# PWM_CONTROL.net
KiCad netlist of a schematic drawn in Altium Designer
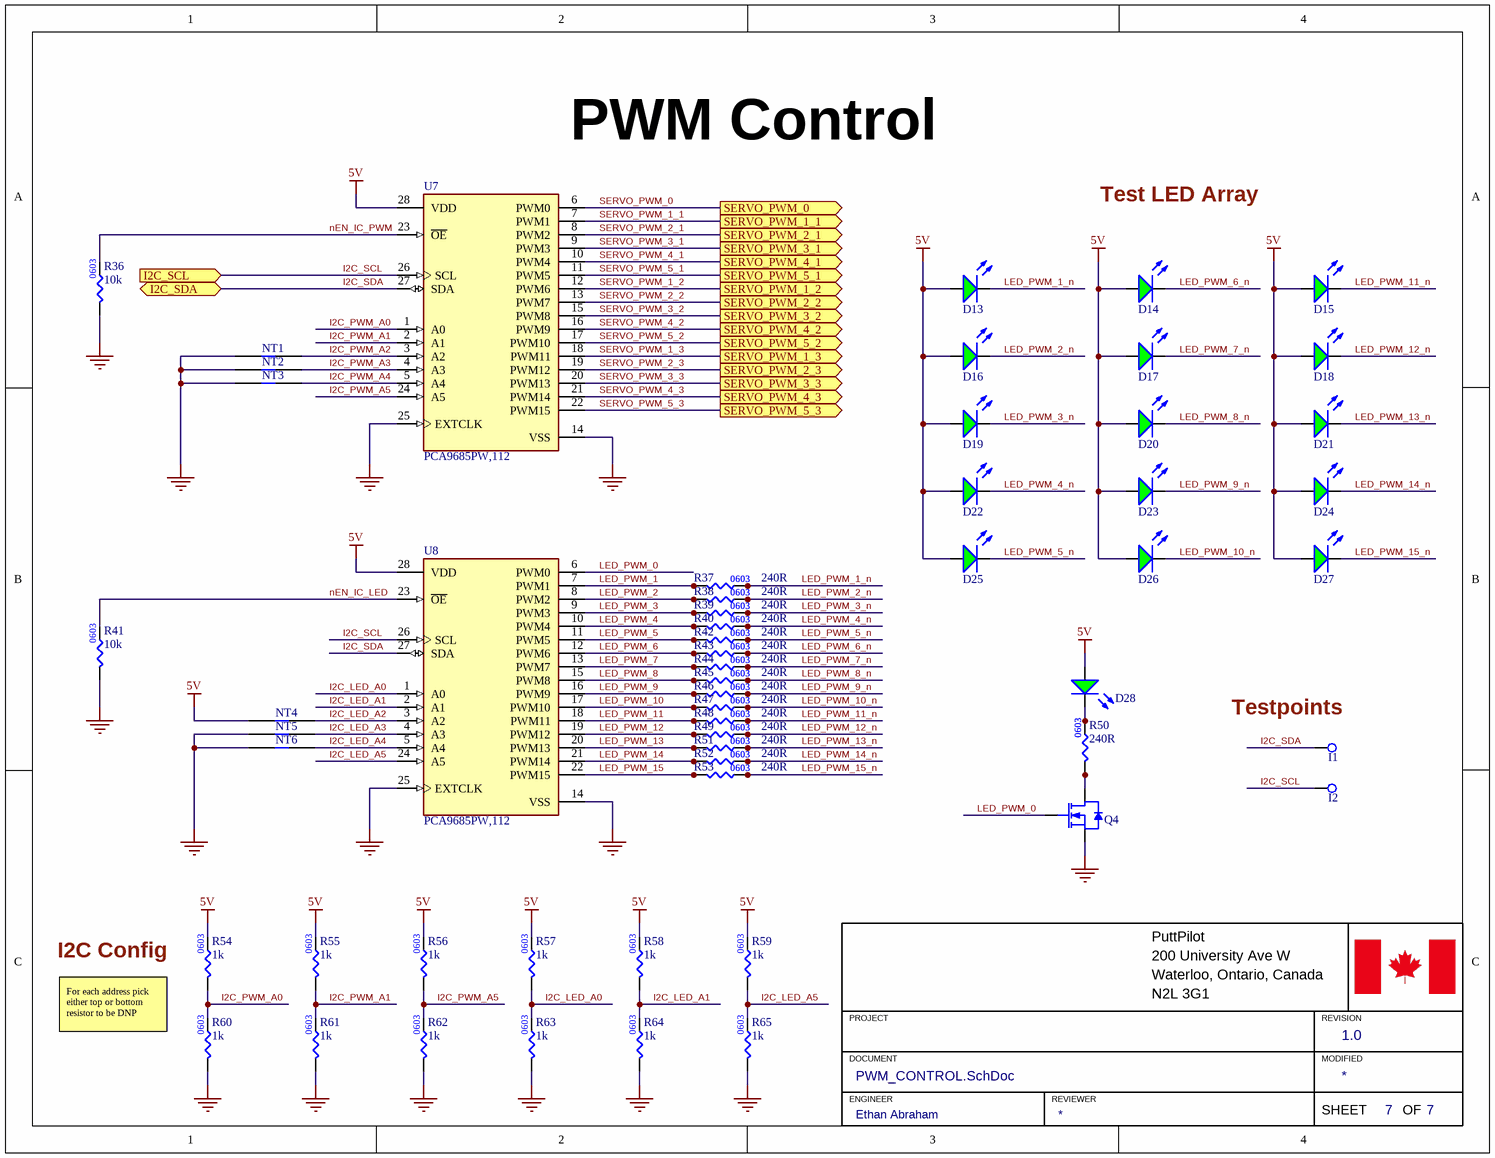
[diagram p0: PWM_CONTROL.SchDoc]

(export (version "E")
  (design (tool "Eeschema 10.0.6"))
  (components
    (comp (ref "D13")
      (value "LTST-C191KGKT")
      (footprint ".LED_0603")
      (description "LED GREEN 2V 0603")
      (fields (field (name "MANUFACTURER") "Vishay Lite-On"))
      (libsource (lib "PuttPilot") (part "LTST-C191KGKT"))
    )
    (comp (ref "D14")
      (value "LTST-C191KGKT")
      (footprint ".LED_0603")
      (description "LED GREEN 2V 0603")
      (fields (field (name "MANUFACTURER") "Vishay Lite-On"))
      (libsource (lib "PuttPilot") (part "LTST-C191KGKT"))
    )
    (comp (ref "D15")
      (value "LTST-C191KGKT")
      (footprint ".LED_0603")
      (description "LED GREEN 2V 0603")
      (fields (field (name "MANUFACTURER") "Vishay Lite-On"))
      (libsource (lib "PuttPilot") (part "LTST-C191KGKT"))
    )
    (comp (ref "D16")
      (value "LTST-C191KGKT")
      (footprint ".LED_0603")
      (description "LED GREEN 2V 0603")
      (fields (field (name "MANUFACTURER") "Vishay Lite-On"))
      (libsource (lib "PuttPilot") (part "LTST-C191KGKT"))
    )
    (comp (ref "D17")
      (value "LTST-C191KGKT")
      (footprint ".LED_0603")
      (description "LED GREEN 2V 0603")
      (fields (field (name "MANUFACTURER") "Vishay Lite-On"))
      (libsource (lib "PuttPilot") (part "LTST-C191KGKT"))
    )
    (comp (ref "D18")
      (value "LTST-C191KGKT")
      (footprint ".LED_0603")
      (description "LED GREEN 2V 0603")
      (fields (field (name "MANUFACTURER") "Vishay Lite-On"))
      (libsource (lib "PuttPilot") (part "LTST-C191KGKT"))
    )
    (comp (ref "D19")
      (value "LTST-C191KGKT")
      (footprint ".LED_0603")
      (description "LED GREEN 2V 0603")
      (fields (field (name "MANUFACTURER") "Vishay Lite-On"))
      (libsource (lib "PuttPilot") (part "LTST-C191KGKT"))
    )
    (comp (ref "D20")
      (value "LTST-C191KGKT")
      (footprint ".LED_0603")
      (description "LED GREEN 2V 0603")
      (fields (field (name "MANUFACTURER") "Vishay Lite-On"))
      (libsource (lib "PuttPilot") (part "LTST-C191KGKT"))
    )
    (comp (ref "D21")
      (value "LTST-C191KGKT")
      (footprint ".LED_0603")
      (description "LED GREEN 2V 0603")
      (fields (field (name "MANUFACTURER") "Vishay Lite-On"))
      (libsource (lib "PuttPilot") (part "LTST-C191KGKT"))
    )
    (comp (ref "D22")
      (value "LTST-C191KGKT")
      (footprint ".LED_0603")
      (description "LED GREEN 2V 0603")
      (fields (field (name "MANUFACTURER") "Vishay Lite-On"))
      (libsource (lib "PuttPilot") (part "LTST-C191KGKT"))
    )
    (comp (ref "D23")
      (value "LTST-C191KGKT")
      (footprint ".LED_0603")
      (description "LED GREEN 2V 0603")
      (fields (field (name "MANUFACTURER") "Vishay Lite-On"))
      (libsource (lib "PuttPilot") (part "LTST-C191KGKT"))
    )
    (comp (ref "D24")
      (value "LTST-C191KGKT")
      (footprint ".LED_0603")
      (description "LED GREEN 2V 0603")
      (fields (field (name "MANUFACTURER") "Vishay Lite-On"))
      (libsource (lib "PuttPilot") (part "LTST-C191KGKT"))
    )
    (comp (ref "D25")
      (value "LTST-C191KGKT")
      (footprint ".LED_0603")
      (description "LED GREEN 2V 0603")
      (fields (field (name "MANUFACTURER") "Vishay Lite-On"))
      (libsource (lib "PuttPilot") (part "LTST-C191KGKT"))
    )
    (comp (ref "D26")
      (value "LTST-C191KGKT")
      (footprint ".LED_0603")
      (description "LED GREEN 2V 0603")
      (fields (field (name "MANUFACTURER") "Vishay Lite-On"))
      (libsource (lib "PuttPilot") (part "LTST-C191KGKT"))
    )
    (comp (ref "D27")
      (value "LTST-C191KGKT")
      (footprint ".LED_0603")
      (description "LED GREEN 2V 0603")
      (fields (field (name "MANUFACTURER") "Vishay Lite-On"))
      (libsource (lib "PuttPilot") (part "LTST-C191KGKT"))
    )
    (comp (ref "D28")
      (value "LTST-C191KGKT")
      (footprint ".LED_0603")
      (description "LED GREEN 2V 0603")
      (fields (field (name "MANUFACTURER") "Vishay Lite-On"))
      (libsource (lib "PuttPilot") (part "LTST-C191KGKT"))
    )
    (comp (ref "I1")
      (value "RCWCTE")
      (footprint "RCWCTE")
      (description "SMT Test Point")
      (fields (field (name "MANUFACTURER") "KOA Speer"))
      (libsource (lib "PuttPilot") (part "RCWCTE"))
    )
    (comp (ref "I2")
      (value "RCWCTE")
      (footprint "RCWCTE")
      (description "SMT Test Point")
      (fields (field (name "MANUFACTURER") "KOA Speer"))
      (libsource (lib "PuttPilot") (part "RCWCTE"))
    )
    (comp (ref "NT1")
      (value ".NET_TIE")
      (footprint ".NET_TIE")
      (description ".GENERIC NET TIE")
      (libsource (lib "PuttPilot") (part ".NET_TIE"))
    )
    (comp (ref "NT2")
      (value ".NET_TIE")
      (footprint ".NET_TIE")
      (description ".GENERIC NET TIE")
      (libsource (lib "PuttPilot") (part ".NET_TIE"))
    )
    (comp (ref "NT3")
      (value ".NET_TIE")
      (footprint ".NET_TIE")
      (description ".GENERIC NET TIE")
      (libsource (lib "PuttPilot") (part ".NET_TIE"))
    )
    (comp (ref "NT4")
      (value ".NET_TIE")
      (footprint ".NET_TIE")
      (description ".GENERIC NET TIE")
      (libsource (lib "PuttPilot") (part ".NET_TIE"))
    )
    (comp (ref "NT5")
      (value ".NET_TIE")
      (footprint ".NET_TIE")
      (description ".GENERIC NET TIE")
      (libsource (lib "PuttPilot") (part ".NET_TIE"))
    )
    (comp (ref "NT6")
      (value ".NET_TIE")
      (footprint ".NET_TIE")
      (description ".GENERIC NET TIE")
      (libsource (lib "PuttPilot") (part ".NET_TIE"))
    )
    (comp (ref "Q4")
      (value "DMN6140L-7")
      (footprint ".SOT-23-3")
      (description "MOSFET N-CH 60V 1.6A SOT-23")
      (fields (field (name "MANUFACTURER") "Diodes"))
      (libsource (lib "PuttPilot") (part "DMN6140L-7"))
    )
    (comp (ref "R36")
      (value "RC0603FR-0710KL")
      (footprint ".RES_0603")
      (description "RES 10K OHM 0603")
      (fields
        (field (name "MANUFACTURER") "Yageo")
        (field (name "TOLERANCE") "1%")
        (field (name "RESISTANCE") "10k")
      )
      (libsource (lib "PuttPilot") (part "RC0603FR-0710KL"))
    )
    (comp (ref "R37")
      (value "RC0603FR-07240RL")
      (footprint ".RES_0603")
      (description "RES 240 OHM 0603")
      (fields
        (field (name "MANUFACTURER") "Yageo")
        (field (name "TOLERANCE") "1%")
        (field (name "RESISTANCE") "240R")
      )
      (libsource (lib "PuttPilot") (part "RC0603FR-07240RL"))
    )
    (comp (ref "R38")
      (value "RC0603FR-07240RL")
      (footprint ".RES_0603")
      (description "RES 240 OHM 0603")
      (fields
        (field (name "MANUFACTURER") "Yageo")
        (field (name "TOLERANCE") "1%")
        (field (name "RESISTANCE") "240R")
      )
      (libsource (lib "PuttPilot") (part "RC0603FR-07240RL"))
    )
    (comp (ref "R39")
      (value "RC0603FR-07240RL")
      (footprint ".RES_0603")
      (description "RES 240 OHM 0603")
      (fields
        (field (name "MANUFACTURER") "Yageo")
        (field (name "TOLERANCE") "1%")
        (field (name "RESISTANCE") "240R")
      )
      (libsource (lib "PuttPilot") (part "RC0603FR-07240RL"))
    )
    (comp (ref "R40")
      (value "RC0603FR-07240RL")
      (footprint ".RES_0603")
      (description "RES 240 OHM 0603")
      (fields
        (field (name "MANUFACTURER") "Yageo")
        (field (name "TOLERANCE") "1%")
        (field (name "RESISTANCE") "240R")
      )
      (libsource (lib "PuttPilot") (part "RC0603FR-07240RL"))
    )
    (comp (ref "R41")
      (value "RC0603FR-0710KL")
      (footprint ".RES_0603")
      (description "RES 10K OHM 0603")
      (fields
        (field (name "MANUFACTURER") "Yageo")
        (field (name "TOLERANCE") "1%")
        (field (name "RESISTANCE") "10k")
      )
      (libsource (lib "PuttPilot") (part "RC0603FR-0710KL"))
    )
    (comp (ref "R42")
      (value "RC0603FR-07240RL")
      (footprint ".RES_0603")
      (description "RES 240 OHM 0603")
      (fields
        (field (name "MANUFACTURER") "Yageo")
        (field (name "TOLERANCE") "1%")
        (field (name "RESISTANCE") "240R")
      )
      (libsource (lib "PuttPilot") (part "RC0603FR-07240RL"))
    )
    (comp (ref "R43")
      (value "RC0603FR-07240RL")
      (footprint ".RES_0603")
      (description "RES 240 OHM 0603")
      (fields
        (field (name "MANUFACTURER") "Yageo")
        (field (name "TOLERANCE") "1%")
        (field (name "RESISTANCE") "240R")
      )
      (libsource (lib "PuttPilot") (part "RC0603FR-07240RL"))
    )
    (comp (ref "R44")
      (value "RC0603FR-07240RL")
      (footprint ".RES_0603")
      (description "RES 240 OHM 0603")
      (fields
        (field (name "MANUFACTURER") "Yageo")
        (field (name "TOLERANCE") "1%")
        (field (name "RESISTANCE") "240R")
      )
      (libsource (lib "PuttPilot") (part "RC0603FR-07240RL"))
    )
    (comp (ref "R45")
      (value "RC0603FR-07240RL")
      (footprint ".RES_0603")
      (description "RES 240 OHM 0603")
      (fields
        (field (name "MANUFACTURER") "Yageo")
        (field (name "TOLERANCE") "1%")
        (field (name "RESISTANCE") "240R")
      )
      (libsource (lib "PuttPilot") (part "RC0603FR-07240RL"))
    )
    (comp (ref "R46")
      (value "RC0603FR-07240RL")
      (footprint ".RES_0603")
      (description "RES 240 OHM 0603")
      (fields
        (field (name "MANUFACTURER") "Yageo")
        (field (name "TOLERANCE") "1%")
        (field (name "RESISTANCE") "240R")
      )
      (libsource (lib "PuttPilot") (part "RC0603FR-07240RL"))
    )
    (comp (ref "R47")
      (value "RC0603FR-07240RL")
      (footprint ".RES_0603")
      (description "RES 240 OHM 0603")
      (fields
        (field (name "MANUFACTURER") "Yageo")
        (field (name "TOLERANCE") "1%")
        (field (name "RESISTANCE") "240R")
      )
      (libsource (lib "PuttPilot") (part "RC0603FR-07240RL"))
    )
    (comp (ref "R48")
      (value "RC0603FR-07240RL")
      (footprint ".RES_0603")
      (description "RES 240 OHM 0603")
      (fields
        (field (name "MANUFACTURER") "Yageo")
        (field (name "TOLERANCE") "1%")
        (field (name "RESISTANCE") "240R")
      )
      (libsource (lib "PuttPilot") (part "RC0603FR-07240RL"))
    )
    (comp (ref "R49")
      (value "RC0603FR-07240RL")
      (footprint ".RES_0603")
      (description "RES 240 OHM 0603")
      (fields
        (field (name "MANUFACTURER") "Yageo")
        (field (name "TOLERANCE") "1%")
        (field (name "RESISTANCE") "240R")
      )
      (libsource (lib "PuttPilot") (part "RC0603FR-07240RL"))
    )
    (comp (ref "R50")
      (value "RC0603FR-07240RL")
      (footprint ".RES_0603")
      (description "RES 240 OHM 0603")
      (fields
        (field (name "MANUFACTURER") "Yageo")
        (field (name "TOLERANCE") "1%")
        (field (name "RESISTANCE") "240R")
      )
      (libsource (lib "PuttPilot") (part "RC0603FR-07240RL"))
    )
    (comp (ref "R51")
      (value "RC0603FR-07240RL")
      (footprint ".RES_0603")
      (description "RES 240 OHM 0603")
      (fields
        (field (name "MANUFACTURER") "Yageo")
        (field (name "TOLERANCE") "1%")
        (field (name "RESISTANCE") "240R")
      )
      (libsource (lib "PuttPilot") (part "RC0603FR-07240RL"))
    )
    (comp (ref "R52")
      (value "RC0603FR-07240RL")
      (footprint ".RES_0603")
      (description "RES 240 OHM 0603")
      (fields
        (field (name "MANUFACTURER") "Yageo")
        (field (name "TOLERANCE") "1%")
        (field (name "RESISTANCE") "240R")
      )
      (libsource (lib "PuttPilot") (part "RC0603FR-07240RL"))
    )
    (comp (ref "R53")
      (value "RC0603FR-07240RL")
      (footprint ".RES_0603")
      (description "RES 240 OHM 0603")
      (fields
        (field (name "MANUFACTURER") "Yageo")
        (field (name "TOLERANCE") "1%")
        (field (name "RESISTANCE") "240R")
      )
      (libsource (lib "PuttPilot") (part "RC0603FR-07240RL"))
    )
    (comp (ref "R54")
      (value "RC0603FR-071KL")
      (footprint ".RES_0603")
      (description "RES 1K OHM 0603")
      (fields
        (field (name "MANUFACTURER") "Yageo")
        (field (name "TOLERANCE") "1%")
        (field (name "RESISTANCE") "1k")
      )
      (libsource (lib "PuttPilot") (part "RC0603FR-071KL"))
    )
    (comp (ref "R55")
      (value "RC0603FR-071KL")
      (footprint ".RES_0603")
      (description "RES 1K OHM 0603")
      (fields
        (field (name "MANUFACTURER") "Yageo")
        (field (name "TOLERANCE") "1%")
        (field (name "RESISTANCE") "1k")
      )
      (libsource (lib "PuttPilot") (part "RC0603FR-071KL"))
    )
    (comp (ref "R56")
      (value "RC0603FR-071KL")
      (footprint ".RES_0603")
      (description "RES 1K OHM 0603")
      (fields
        (field (name "MANUFACTURER") "Yageo")
        (field (name "TOLERANCE") "1%")
        (field (name "RESISTANCE") "1k")
      )
      (libsource (lib "PuttPilot") (part "RC0603FR-071KL"))
    )
    (comp (ref "R57")
      (value "RC0603FR-071KL")
      (footprint ".RES_0603")
      (description "RES 1K OHM 0603")
      (fields
        (field (name "MANUFACTURER") "Yageo")
        (field (name "TOLERANCE") "1%")
        (field (name "RESISTANCE") "1k")
      )
      (libsource (lib "PuttPilot") (part "RC0603FR-071KL"))
    )
    (comp (ref "R58")
      (value "RC0603FR-071KL")
      (footprint ".RES_0603")
      (description "RES 1K OHM 0603")
      (fields
        (field (name "MANUFACTURER") "Yageo")
        (field (name "TOLERANCE") "1%")
        (field (name "RESISTANCE") "1k")
      )
      (libsource (lib "PuttPilot") (part "RC0603FR-071KL"))
    )
    (comp (ref "R59")
      (value "RC0603FR-071KL")
      (footprint ".RES_0603")
      (description "RES 1K OHM 0603")
      (fields
        (field (name "MANUFACTURER") "Yageo")
        (field (name "TOLERANCE") "1%")
        (field (name "RESISTANCE") "1k")
      )
      (libsource (lib "PuttPilot") (part "RC0603FR-071KL"))
    )
    (comp (ref "R60")
      (value "RC0603FR-071KL")
      (footprint ".RES_0603")
      (description "RES 1K OHM 0603")
      (fields
        (field (name "MANUFACTURER") "Yageo")
        (field (name "TOLERANCE") "1%")
        (field (name "RESISTANCE") "1k")
      )
      (libsource (lib "PuttPilot") (part "RC0603FR-071KL"))
    )
    (comp (ref "R61")
      (value "RC0603FR-071KL")
      (footprint ".RES_0603")
      (description "RES 1K OHM 0603")
      (fields
        (field (name "MANUFACTURER") "Yageo")
        (field (name "TOLERANCE") "1%")
        (field (name "RESISTANCE") "1k")
      )
      (libsource (lib "PuttPilot") (part "RC0603FR-071KL"))
    )
    (comp (ref "R62")
      (value "RC0603FR-071KL")
      (footprint ".RES_0603")
      (description "RES 1K OHM 0603")
      (fields
        (field (name "MANUFACTURER") "Yageo")
        (field (name "TOLERANCE") "1%")
        (field (name "RESISTANCE") "1k")
      )
      (libsource (lib "PuttPilot") (part "RC0603FR-071KL"))
    )
    (comp (ref "R63")
      (value "RC0603FR-071KL")
      (footprint ".RES_0603")
      (description "RES 1K OHM 0603")
      (fields
        (field (name "MANUFACTURER") "Yageo")
        (field (name "TOLERANCE") "1%")
        (field (name "RESISTANCE") "1k")
      )
      (libsource (lib "PuttPilot") (part "RC0603FR-071KL"))
    )
    (comp (ref "R64")
      (value "RC0603FR-071KL")
      (footprint ".RES_0603")
      (description "RES 1K OHM 0603")
      (fields
        (field (name "MANUFACTURER") "Yageo")
        (field (name "TOLERANCE") "1%")
        (field (name "RESISTANCE") "1k")
      )
      (libsource (lib "PuttPilot") (part "RC0603FR-071KL"))
    )
    (comp (ref "R65")
      (value "RC0603FR-071KL")
      (footprint ".RES_0603")
      (description "RES 1K OHM 0603")
      (fields
        (field (name "MANUFACTURER") "Yageo")
        (field (name "TOLERANCE") "1%")
        (field (name "RESISTANCE") "1k")
      )
      (libsource (lib "PuttPilot") (part "RC0603FR-071KL"))
    )
    (comp (ref "U7")
      (value "PCA9685PW,112")
      (footprint "PCA9685PW,112")
      (description "I2C LED Driver")
      (fields (field (name "MANUFACTURER") "NXP Semiconductors"))
      (libsource (lib "PuttPilot") (part "PCA9685PW,112"))
    )
    (comp (ref "U8")
      (value "PCA9685PW,112")
      (footprint "PCA9685PW,112")
      (description "I2C LED Driver")
      (fields (field (name "MANUFACTURER") "NXP Semiconductors"))
      (libsource (lib "PuttPilot") (part "PCA9685PW,112"))
    )
  )
  (nets
    (net (code "1") (name "/I2C_LED_A0") (class "Default")
      (node (ref "R57") (pin "1") (pinfunction "1_1") (pintype "passive"))
      (node (ref "R63") (pin "2") (pinfunction "2_2") (pintype "passive"))
      (node (ref "U8") (pin "1") (pinfunction "A0_1") (pintype "input"))
    )
    (net (code "2") (name "/I2C_LED_A1") (class "Default")
      (node (ref "R58") (pin "1") (pinfunction "1_1") (pintype "passive"))
      (node (ref "R64") (pin "2") (pinfunction "2_2") (pintype "passive"))
      (node (ref "U8") (pin "2") (pinfunction "A1_2") (pintype "input"))
    )
    (net (code "3") (name "/I2C_LED_A2") (class "Default")
      (node (ref "NT4") (pin "2") (pinfunction "2_2") (pintype "passive"))
      (node (ref "U8") (pin "3") (pinfunction "A2_3") (pintype "input"))
    )
    (net (code "4") (name "/I2C_LED_A3") (class "Default")
      (node (ref "NT5") (pin "2") (pinfunction "2_2") (pintype "passive"))
      (node (ref "U8") (pin "4") (pinfunction "A3_4") (pintype "input"))
    )
    (net (code "5") (name "/I2C_LED_A4") (class "Default")
      (node (ref "NT6") (pin "2") (pinfunction "2_2") (pintype "passive"))
      (node (ref "U8") (pin "5") (pinfunction "A4_5") (pintype "input"))
    )
    (net (code "6") (name "/I2C_LED_A5") (class "Default")
      (node (ref "R59") (pin "1") (pinfunction "1_1") (pintype "passive"))
      (node (ref "R65") (pin "2") (pinfunction "2_2") (pintype "passive"))
      (node (ref "U8") (pin "24") (pinfunction "A5_24") (pintype "input"))
    )
    (net (code "7") (name "/I2C_PWM_A0") (class "Default")
      (node (ref "R54") (pin "1") (pinfunction "1_1") (pintype "passive"))
      (node (ref "R60") (pin "2") (pinfunction "2_2") (pintype "passive"))
      (node (ref "U7") (pin "1") (pinfunction "A0_1") (pintype "input"))
    )
    (net (code "8") (name "/I2C_PWM_A1") (class "Default")
      (node (ref "R55") (pin "1") (pinfunction "1_1") (pintype "passive"))
      (node (ref "R61") (pin "2") (pinfunction "2_2") (pintype "passive"))
      (node (ref "U7") (pin "2") (pinfunction "A1_2") (pintype "input"))
    )
    (net (code "9") (name "/I2C_PWM_A2") (class "Default")
      (node (ref "NT1") (pin "2") (pinfunction "2_2") (pintype "passive"))
      (node (ref "U7") (pin "3") (pinfunction "A2_3") (pintype "input"))
    )
    (net (code "10") (name "/I2C_PWM_A3") (class "Default")
      (node (ref "NT2") (pin "2") (pinfunction "2_2") (pintype "passive"))
      (node (ref "U7") (pin "4") (pinfunction "A3_4") (pintype "input"))
    )
    (net (code "11") (name "/I2C_PWM_A4") (class "Default")
      (node (ref "NT3") (pin "2") (pinfunction "2_2") (pintype "passive"))
      (node (ref "U7") (pin "5") (pinfunction "A4_5") (pintype "input"))
    )
    (net (code "12") (name "/I2C_PWM_A5") (class "Default")
      (node (ref "R56") (pin "1") (pinfunction "1_1") (pintype "passive"))
      (node (ref "R62") (pin "2") (pinfunction "2_2") (pintype "passive"))
      (node (ref "U7") (pin "24") (pinfunction "A5_24") (pintype "input"))
    )
    (net (code "13") (name "/I2C_SCL") (class "Default")
      (node (ref "I2") (pin "1") (pinfunction "1_1") (pintype "passive"))
      (node (ref "U7") (pin "26") (pinfunction "SCL_26") (pintype "input"))
      (node (ref "U8") (pin "26") (pinfunction "SCL_26") (pintype "input"))
    )
    (net (code "14") (name "/I2C_SDA") (class "Default")
      (node (ref "I1") (pin "1") (pinfunction "1_1") (pintype "passive"))
      (node (ref "U7") (pin "27") (pinfunction "SDA_27") (pintype "bidirectional"))
      (node (ref "U8") (pin "27") (pinfunction "SDA_27") (pintype "bidirectional"))
    )
    (net (code "15") (name "/LED_PWM_0") (class "Default")
      (node (ref "Q4") (pin "1") (pinfunction "Gate_1") (pintype "passive"))
      (node (ref "U8") (pin "6") (pinfunction "PWM0_6") (pintype "tri_state"))
    )
    (net (code "16") (name "/LED_PWM_1") (class "Default")
      (node (ref "R37") (pin "1") (pinfunction "1_1") (pintype "passive"))
      (node (ref "U8") (pin "7") (pinfunction "PWM1_7") (pintype "tri_state"))
    )
    (net (code "17") (name "/LED_PWM_1_n") (class "Default")
      (node (ref "D13") (pin "2") (pinfunction "K_2") (pintype "passive"))
      (node (ref "R37") (pin "2") (pinfunction "2_2") (pintype "passive"))
    )
    (net (code "18") (name "/LED_PWM_2") (class "Default")
      (node (ref "R38") (pin "1") (pinfunction "1_1") (pintype "passive"))
      (node (ref "U8") (pin "8") (pinfunction "PWM2_8") (pintype "tri_state"))
    )
    (net (code "19") (name "/LED_PWM_2_n") (class "Default")
      (node (ref "D16") (pin "2") (pinfunction "K_2") (pintype "passive"))
      (node (ref "R38") (pin "2") (pinfunction "2_2") (pintype "passive"))
    )
    (net (code "20") (name "/LED_PWM_3") (class "Default")
      (node (ref "R39") (pin "1") (pinfunction "1_1") (pintype "passive"))
      (node (ref "U8") (pin "9") (pinfunction "PWM3_9") (pintype "tri_state"))
    )
    (net (code "21") (name "/LED_PWM_3_n") (class "Default")
      (node (ref "D19") (pin "2") (pinfunction "K_2") (pintype "passive"))
      (node (ref "R39") (pin "2") (pinfunction "2_2") (pintype "passive"))
    )
    (net (code "22") (name "/LED_PWM_4") (class "Default")
      (node (ref "R40") (pin "1") (pinfunction "1_1") (pintype "passive"))
      (node (ref "U8") (pin "10") (pinfunction "PWM4_10") (pintype "tri_state"))
    )
    (net (code "23") (name "/LED_PWM_4_n") (class "Default")
      (node (ref "D22") (pin "2") (pinfunction "K_2") (pintype "passive"))
      (node (ref "R40") (pin "2") (pinfunction "2_2") (pintype "passive"))
    )
    (net (code "24") (name "/LED_PWM_5") (class "Default")
      (node (ref "R42") (pin "1") (pinfunction "1_1") (pintype "passive"))
      (node (ref "U8") (pin "11") (pinfunction "PWM5_11") (pintype "tri_state"))
    )
    (net (code "25") (name "/LED_PWM_5_n") (class "Default")
      (node (ref "D25") (pin "2") (pinfunction "K_2") (pintype "passive"))
      (node (ref "R42") (pin "2") (pinfunction "2_2") (pintype "passive"))
    )
    (net (code "26") (name "/LED_PWM_6") (class "Default")
      (node (ref "R43") (pin "1") (pinfunction "1_1") (pintype "passive"))
      (node (ref "U8") (pin "12") (pinfunction "PWM6_12") (pintype "tri_state"))
    )
    (net (code "27") (name "/LED_PWM_6_n") (class "Default")
      (node (ref "D14") (pin "2") (pinfunction "K_2") (pintype "passive"))
      (node (ref "R43") (pin "2") (pinfunction "2_2") (pintype "passive"))
    )
    (net (code "28") (name "/LED_PWM_7") (class "Default")
      (node (ref "R44") (pin "1") (pinfunction "1_1") (pintype "passive"))
      (node (ref "U8") (pin "13") (pinfunction "PWM7_13") (pintype "tri_state"))
    )
    (net (code "29") (name "/LED_PWM_7_n") (class "Default")
      (node (ref "D17") (pin "2") (pinfunction "K_2") (pintype "passive"))
      (node (ref "R44") (pin "2") (pinfunction "2_2") (pintype "passive"))
    )
    (net (code "30") (name "/LED_PWM_8") (class "Default")
      (node (ref "R45") (pin "1") (pinfunction "1_1") (pintype "passive"))
      (node (ref "U8") (pin "15") (pinfunction "PWM8_15") (pintype "tri_state"))
    )
    (net (code "31") (name "/LED_PWM_8_n") (class "Default")
      (node (ref "D20") (pin "2") (pinfunction "K_2") (pintype "passive"))
      (node (ref "R45") (pin "2") (pinfunction "2_2") (pintype "passive"))
    )
    (net (code "32") (name "/LED_PWM_9") (class "Default")
      (node (ref "R46") (pin "1") (pinfunction "1_1") (pintype "passive"))
      (node (ref "U8") (pin "16") (pinfunction "PWM9_16") (pintype "tri_state"))
    )
    (net (code "33") (name "/LED_PWM_9_n") (class "Default")
      (node (ref "D23") (pin "2") (pinfunction "K_2") (pintype "passive"))
      (node (ref "R46") (pin "2") (pinfunction "2_2") (pintype "passive"))
    )
    (net (code "34") (name "/LED_PWM_10") (class "Default")
      (node (ref "R47") (pin "1") (pinfunction "1_1") (pintype "passive"))
      (node (ref "U8") (pin "17") (pinfunction "PWM10_17") (pintype "tri_state"))
    )
    (net (code "35") (name "/LED_PWM_10_n") (class "Default")
      (node (ref "D26") (pin "2") (pinfunction "K_2") (pintype "passive"))
      (node (ref "R47") (pin "2") (pinfunction "2_2") (pintype "passive"))
    )
    (net (code "36") (name "/LED_PWM_11") (class "Default")
      (node (ref "R48") (pin "1") (pinfunction "1_1") (pintype "passive"))
      (node (ref "U8") (pin "18") (pinfunction "PWM11_18") (pintype "tri_state"))
    )
    (net (code "37") (name "/LED_PWM_11_n") (class "Default")
      (node (ref "D15") (pin "2") (pinfunction "K_2") (pintype "passive"))
      (node (ref "R48") (pin "2") (pinfunction "2_2") (pintype "passive"))
    )
    (net (code "38") (name "/LED_PWM_12") (class "Default")
      (node (ref "R49") (pin "1") (pinfunction "1_1") (pintype "passive"))
      (node (ref "U8") (pin "19") (pinfunction "PWM12_19") (pintype "tri_state"))
    )
    (net (code "39") (name "/LED_PWM_12_n") (class "Default")
      (node (ref "D18") (pin "2") (pinfunction "K_2") (pintype "passive"))
      (node (ref "R49") (pin "2") (pinfunction "2_2") (pintype "passive"))
    )
    (net (code "40") (name "/LED_PWM_13") (class "Default")
      (node (ref "R51") (pin "1") (pinfunction "1_1") (pintype "passive"))
      (node (ref "U8") (pin "20") (pinfunction "PWM13_20") (pintype "tri_state"))
    )
    (net (code "41") (name "/LED_PWM_13_n") (class "Default")
      (node (ref "D21") (pin "2") (pinfunction "K_2") (pintype "passive"))
      (node (ref "R51") (pin "2") (pinfunction "2_2") (pintype "passive"))
    )
    (net (code "42") (name "/LED_PWM_14") (class "Default")
      (node (ref "R52") (pin "1") (pinfunction "1_1") (pintype "passive"))
      (node (ref "U8") (pin "21") (pinfunction "PWM14_21") (pintype "tri_state"))
    )
    (net (code "43") (name "/LED_PWM_14_n") (class "Default")
      (node (ref "D24") (pin "2") (pinfunction "K_2") (pintype "passive"))
      (node (ref "R52") (pin "2") (pinfunction "2_2") (pintype "passive"))
    )
    (net (code "44") (name "/LED_PWM_15") (class "Default")
      (node (ref "R53") (pin "1") (pinfunction "1_1") (pintype "passive"))
      (node (ref "U8") (pin "22") (pinfunction "PWM15_22") (pintype "tri_state"))
    )
    (net (code "45") (name "/LED_PWM_15_n") (class "Default")
      (node (ref "D27") (pin "2") (pinfunction "K_2") (pintype "passive"))
      (node (ref "R53") (pin "2") (pinfunction "2_2") (pintype "passive"))
    )
    (net (code "46") (name "/SERVO_PWM_0") (class "Default")
      (node (ref "U7") (pin "6") (pinfunction "PWM0_6") (pintype "tri_state"))
    )
    (net (code "47") (name "/SERVO_PWM_1_1") (class "Default")
      (node (ref "U7") (pin "7") (pinfunction "PWM1_7") (pintype "tri_state"))
    )
    (net (code "48") (name "/SERVO_PWM_1_2") (class "Default")
      (node (ref "U7") (pin "12") (pinfunction "PWM6_12") (pintype "tri_state"))
    )
    (net (code "49") (name "/SERVO_PWM_1_3") (class "Default")
      (node (ref "U7") (pin "18") (pinfunction "PWM11_18") (pintype "tri_state"))
    )
    (net (code "50") (name "/SERVO_PWM_2_1") (class "Default")
      (node (ref "U7") (pin "8") (pinfunction "PWM2_8") (pintype "tri_state"))
    )
    (net (code "51") (name "/SERVO_PWM_2_2") (class "Default")
      (node (ref "U7") (pin "13") (pinfunction "PWM7_13") (pintype "tri_state"))
    )
    (net (code "52") (name "/SERVO_PWM_2_3") (class "Default")
      (node (ref "U7") (pin "19") (pinfunction "PWM12_19") (pintype "tri_state"))
    )
    (net (code "53") (name "/SERVO_PWM_3_1") (class "Default")
      (node (ref "U7") (pin "9") (pinfunction "PWM3_9") (pintype "tri_state"))
    )
    (net (code "54") (name "/SERVO_PWM_3_2") (class "Default")
      (node (ref "U7") (pin "15") (pinfunction "PWM8_15") (pintype "tri_state"))
    )
    (net (code "55") (name "/SERVO_PWM_3_3") (class "Default")
      (node (ref "U7") (pin "20") (pinfunction "PWM13_20") (pintype "tri_state"))
    )
    (net (code "56") (name "/SERVO_PWM_4_1") (class "Default")
      (node (ref "U7") (pin "10") (pinfunction "PWM4_10") (pintype "tri_state"))
    )
    (net (code "57") (name "/SERVO_PWM_4_2") (class "Default")
      (node (ref "U7") (pin "16") (pinfunction "PWM9_16") (pintype "tri_state"))
    )
    (net (code "58") (name "/SERVO_PWM_4_3") (class "Default")
      (node (ref "U7") (pin "21") (pinfunction "PWM14_21") (pintype "tri_state"))
    )
    (net (code "59") (name "/SERVO_PWM_5_1") (class "Default")
      (node (ref "U7") (pin "11") (pinfunction "PWM5_11") (pintype "tri_state"))
    )
    (net (code "60") (name "/SERVO_PWM_5_2") (class "Default")
      (node (ref "U7") (pin "17") (pinfunction "PWM10_17") (pintype "tri_state"))
    )
    (net (code "61") (name "/SERVO_PWM_5_3") (class "Default")
      (node (ref "U7") (pin "22") (pinfunction "PWM15_22") (pintype "tri_state"))
    )
    (net (code "62") (name "/nEN_IC_LED") (class "Default")
      (node (ref "R41") (pin "2") (pinfunction "2_2") (pintype "passive"))
      (node (ref "U8") (pin "23") (pinfunction "~{OE}_23") (pintype "input"))
    )
    (net (code "63") (name "/nEN_IC_PWM") (class "Default")
      (node (ref "R36") (pin "2") (pinfunction "2_2") (pintype "passive"))
      (node (ref "U7") (pin "23") (pinfunction "~{OE}_23") (pintype "input"))
    )
    (net (code "64") (name "5V") (class "Default")
      (node (ref "D13") (pin "1") (pinfunction "A_1") (pintype "passive"))
      (node (ref "D14") (pin "1") (pinfunction "A_1") (pintype "passive"))
      (node (ref "D15") (pin "1") (pinfunction "A_1") (pintype "passive"))
      (node (ref "D16") (pin "1") (pinfunction "A_1") (pintype "passive"))
      (node (ref "D17") (pin "1") (pinfunction "A_1") (pintype "passive"))
      (node (ref "D18") (pin "1") (pinfunction "A_1") (pintype "passive"))
      (node (ref "D19") (pin "1") (pinfunction "A_1") (pintype "passive"))
      (node (ref "D20") (pin "1") (pinfunction "A_1") (pintype "passive"))
      (node (ref "D21") (pin "1") (pinfunction "A_1") (pintype "passive"))
      (node (ref "D22") (pin "1") (pinfunction "A_1") (pintype "passive"))
      (node (ref "D23") (pin "1") (pinfunction "A_1") (pintype "passive"))
      (node (ref "D24") (pin "1") (pinfunction "A_1") (pintype "passive"))
      (node (ref "D25") (pin "1") (pinfunction "A_1") (pintype "passive"))
      (node (ref "D26") (pin "1") (pinfunction "A_1") (pintype "passive"))
      (node (ref "D27") (pin "1") (pinfunction "A_1") (pintype "passive"))
      (node (ref "D28") (pin "1") (pinfunction "A_1") (pintype "passive"))
      (node (ref "NT4") (pin "1") (pinfunction "1_1") (pintype "passive"))
      (node (ref "R54") (pin "2") (pinfunction "2_2") (pintype "passive"))
      (node (ref "R55") (pin "2") (pinfunction "2_2") (pintype "passive"))
      (node (ref "R56") (pin "2") (pinfunction "2_2") (pintype "passive"))
      (node (ref "R57") (pin "2") (pinfunction "2_2") (pintype "passive"))
      (node (ref "R58") (pin "2") (pinfunction "2_2") (pintype "passive"))
      (node (ref "R59") (pin "2") (pinfunction "2_2") (pintype "passive"))
      (node (ref "U7") (pin "28") (pinfunction "VDD_28") (pintype "power_in"))
      (node (ref "U8") (pin "28") (pinfunction "VDD_28") (pintype "power_in"))
    )
    (net (code "65") (name "GND") (class "Default")
      (node (ref "NT1") (pin "1") (pinfunction "1_1") (pintype "passive"))
      (node (ref "NT2") (pin "1") (pinfunction "1_1") (pintype "passive"))
      (node (ref "NT3") (pin "1") (pinfunction "1_1") (pintype "passive"))
      (node (ref "NT5") (pin "1") (pinfunction "1_1") (pintype "passive"))
      (node (ref "NT6") (pin "1") (pinfunction "1_1") (pintype "passive"))
      (node (ref "Q4") (pin "2") (pinfunction "Source_2") (pintype "passive"))
      (node (ref "R36") (pin "1") (pinfunction "1_1") (pintype "passive"))
      (node (ref "R41") (pin "1") (pinfunction "1_1") (pintype "passive"))
      (node (ref "R60") (pin "1") (pinfunction "1_1") (pintype "passive"))
      (node (ref "R61") (pin "1") (pinfunction "1_1") (pintype "passive"))
      (node (ref "R62") (pin "1") (pinfunction "1_1") (pintype "passive"))
      (node (ref "R63") (pin "1") (pinfunction "1_1") (pintype "passive"))
      (node (ref "R64") (pin "1") (pinfunction "1_1") (pintype "passive"))
      (node (ref "R65") (pin "1") (pinfunction "1_1") (pintype "passive"))
      (node (ref "U7") (pin "14") (pinfunction "VSS_14") (pintype "power_in"))
      (node (ref "U7") (pin "25") (pinfunction "EXTCLK_25") (pintype "input"))
      (node (ref "U8") (pin "14") (pinfunction "VSS_14") (pintype "power_in"))
      (node (ref "U8") (pin "25") (pinfunction "EXTCLK_25") (pintype "input"))
    )
    (net (code "66") (name "Net-(D28-K)") (class "Default")
      (node (ref "D28") (pin "2") (pinfunction "K_2") (pintype "passive"))
      (node (ref "R50") (pin "2") (pinfunction "2_2") (pintype "passive"))
    )
    (net (code "67") (name "Net-(Q4-Drain)") (class "Default")
      (node (ref "Q4") (pin "3") (pinfunction "Drain_3") (pintype "passive"))
      (node (ref "R50") (pin "1") (pinfunction "1_1") (pintype "passive"))
    )
  )
)
